# walrus.net
KiCad netlist of a schematic drawn in EAGLE
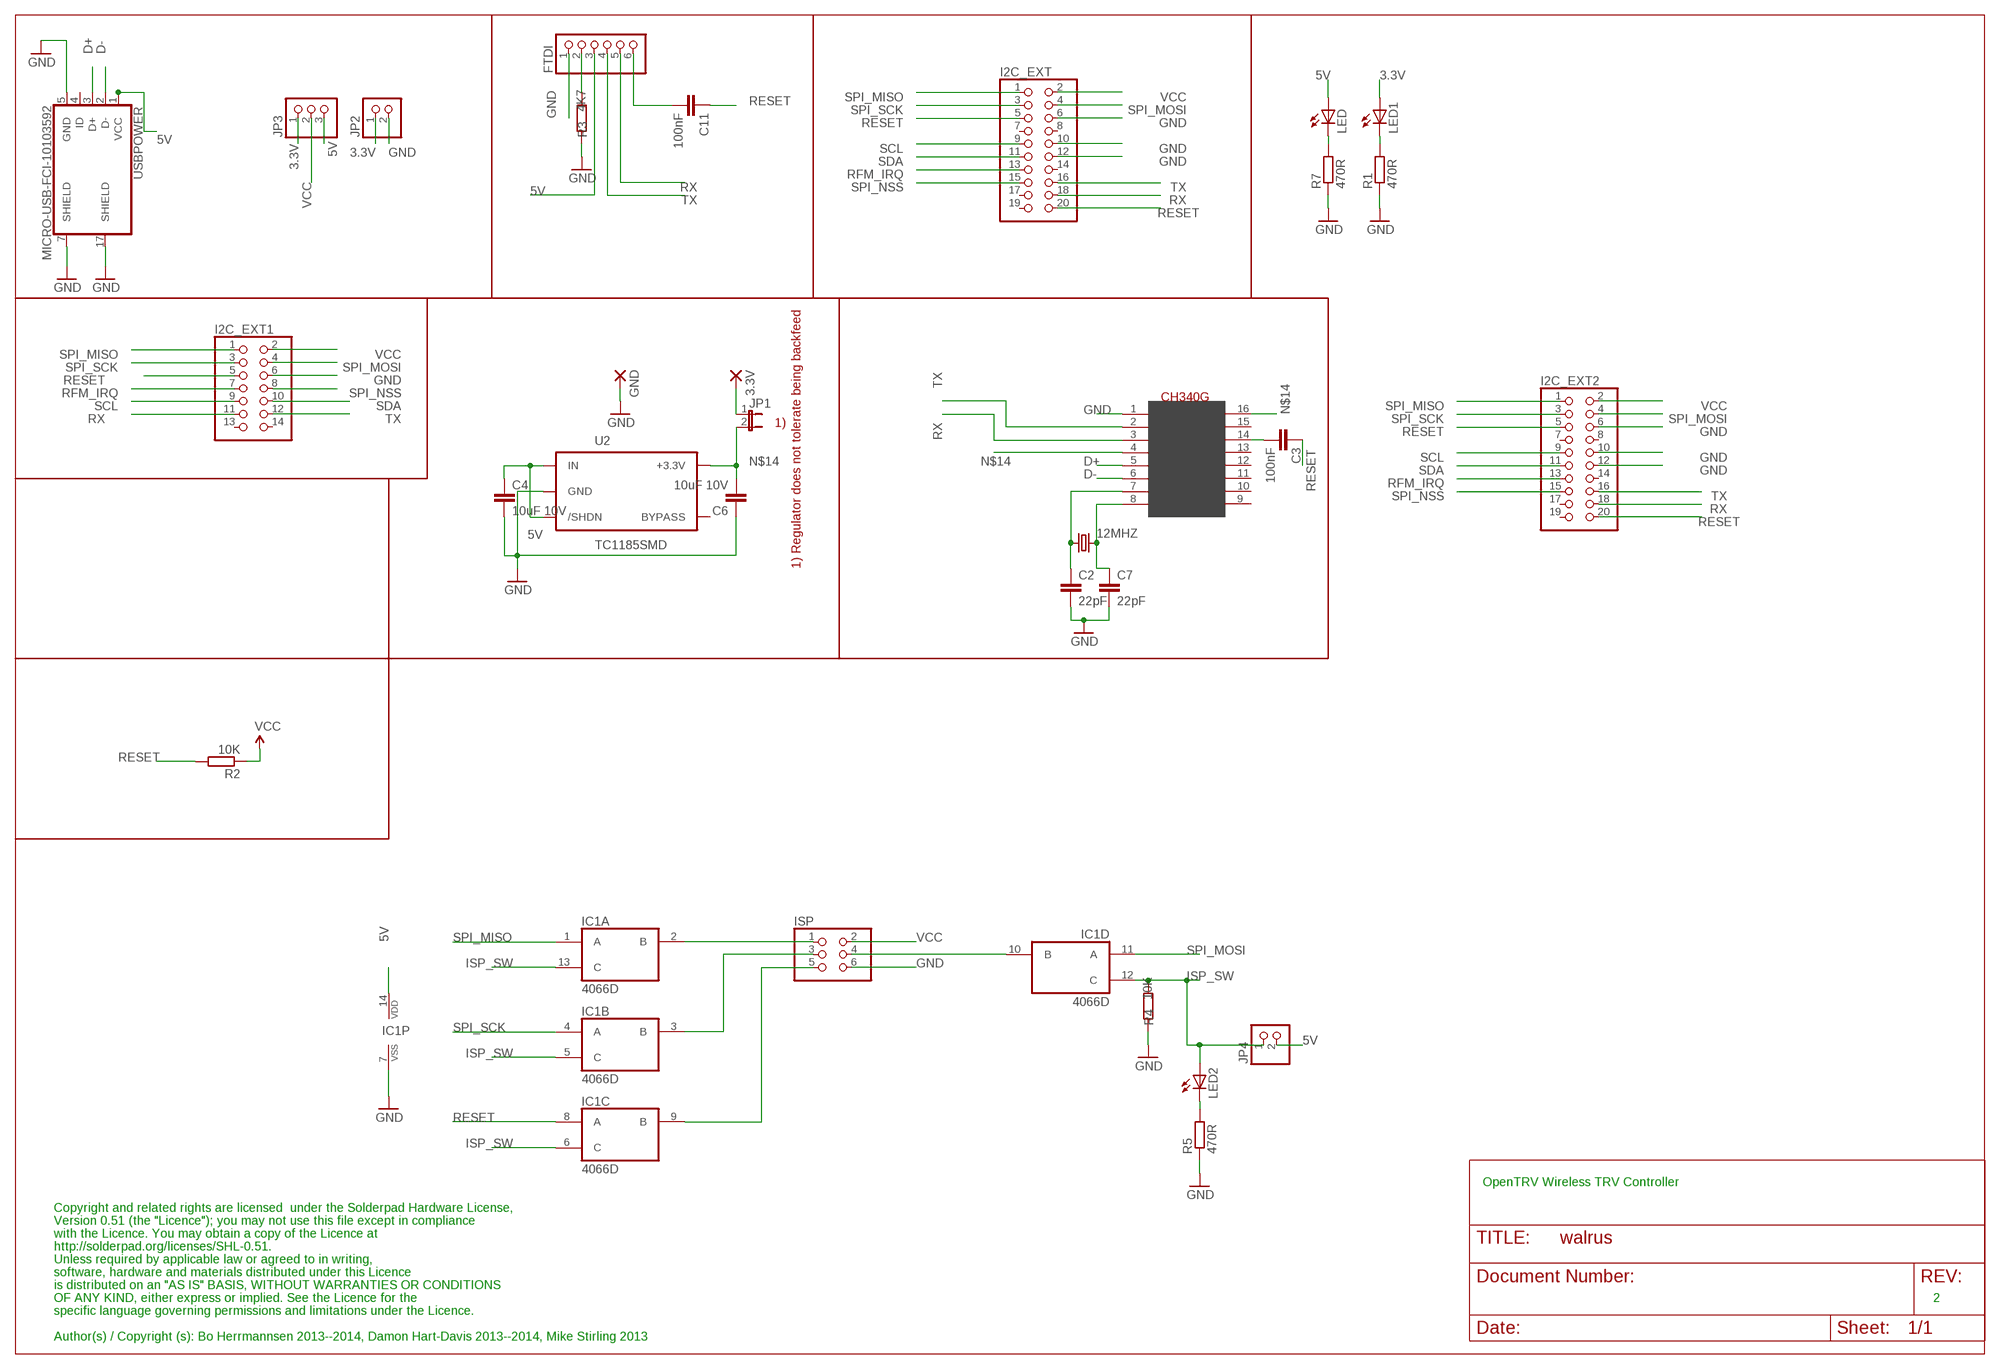
[diagram p0: schematic, sheet 1]

(export (version "E")
  (design (tool "Eeschema 10.0.6"))
  (components
    (comp (ref "3.3V")
      (value "3,81/1,4")
      (footprint "eagle-import:3,81_1,4")
      (libsource (lib "eagle-import") (part "3,81/1,4"))
    )
    (comp (ref "12MHZ")
      (value "CRYSTALHC18U-V")
      (footprint "eagle-import:HC18U-V")
      (libsource (lib "eagle-import") (part "CRYSTALHC18U-V"))
    )
    (comp (ref "C2")
      (value "22pF")
      (footprint "eagle-import:C0603")
      (libsource (lib "eagle-import") (part "C-EUC0603"))
    )
    (comp (ref "C3")
      (value "100nF")
      (footprint "eagle-import:0603-CAP")
      (libsource (lib "eagle-import") (part "CAP0603-CAP"))
    )
    (comp (ref "C4")
      (value "10uF 10V")
      (footprint "eagle-import:0603-CAP")
      (libsource (lib "eagle-import") (part "CAP0603-CAP"))
    )
    (comp (ref "C6")
      (value "10uF 10V")
      (footprint "eagle-import:0603-CAP")
      (libsource (lib "eagle-import") (part "CAP0603-CAP"))
    )
    (comp (ref "C7")
      (value "22pF")
      (footprint "eagle-import:C0603")
      (libsource (lib "eagle-import") (part "C-EUC0603"))
    )
    (comp (ref "C11")
      (value "100nF")
      (footprint "eagle-import:0603-CAP")
      (libsource (lib "eagle-import") (part "CAP0603-CAP"))
    )
    (comp (ref "FTDI")
      (value "PINHD-1X6/90")
      (footprint "eagle-import:1X06_90")
      (libsource (lib "eagle-import") (part "PINHD-1X6/90"))
    )
    (comp (ref "GND")
      (value "3,81/1,4")
      (footprint "eagle-import:3,81_1,4")
      (libsource (lib "eagle-import") (part "3,81/1,4"))
    )
    (comp (ref "I2C_EXT")
      (value "PINHD-2X10")
      (footprint "eagle-import:2X10")
      (libsource (lib "eagle-import") (part "PINHD-2X10"))
    )
    (comp (ref "I2C_EXT1")
      (value "PINHD-2X7")
      (footprint "eagle-import:2X07")
      (libsource (lib "eagle-import") (part "PINHD-2X7"))
    )
    (comp (ref "I2C_EXT2")
      (value "PINHD-2X10")
      (footprint "eagle-import:2X10")
      (libsource (lib "eagle-import") (part "PINHD-2X10"))
    )
    (comp (ref "IC1")
      (value "4066D")
      (footprint "eagle-import:SO14")
      (libsource (lib "eagle-import") (part "4066D"))
    )
    (comp (ref "ISP")
      (value "PINHD-2X3")
      (footprint "eagle-import:2X03")
      (libsource (lib "eagle-import") (part "PINHD-2X3"))
    )
    (comp (ref "JP1")
      (value "JP1E")
      (footprint "eagle-import:JP1")
      (libsource (lib "eagle-import") (part "JP1E"))
    )
    (comp (ref "JP2")
      (value "PINHD-1X2")
      (footprint "eagle-import:1X02")
      (libsource (lib "eagle-import") (part "PINHD-1X2"))
    )
    (comp (ref "JP3")
      (value "PINHD-1X3")
      (footprint "eagle-import:1X03")
      (libsource (lib "eagle-import") (part "PINHD-1X3"))
    )
    (comp (ref "JP4")
      (value "PINHD-1X2")
      (footprint "eagle-import:1X02")
      (libsource (lib "eagle-import") (part "PINHD-1X2"))
    )
    (comp (ref "LED")
      (value "LEDCHIP-LED0603")
      (footprint "eagle-import:CHIP-LED0603")
      (libsource (lib "eagle-import") (part "LEDCHIP-LED0603"))
    )
    (comp (ref "LED1")
      (value "LEDCHIP-LED0603")
      (footprint "eagle-import:CHIP-LED0603")
      (libsource (lib "eagle-import") (part "LEDCHIP-LED0603"))
    )
    (comp (ref "LED2")
      (value "LEDCHIP-LED0603")
      (footprint "eagle-import:CHIP-LED0603")
      (libsource (lib "eagle-import") (part "LEDCHIP-LED0603"))
    )
    (comp (ref "R1")
      (value "470R")
      (footprint "eagle-import:R0603")
      (libsource (lib "eagle-import") (part "R-EU_R0603"))
    )
    (comp (ref "R2")
      (value "10K")
      (footprint "eagle-import:R0603")
      (libsource (lib "eagle-import") (part "R-EU_R0603"))
    )
    (comp (ref "R3")
      (value "4K7")
      (footprint "eagle-import:R0603")
      (libsource (lib "eagle-import") (part "R-EU_R0603"))
    )
    (comp (ref "R4")
      (value "10K")
      (footprint "eagle-import:R0603")
      (libsource (lib "eagle-import") (part "R-EU_R0603"))
    )
    (comp (ref "R5")
      (value "470R")
      (footprint "eagle-import:R0603")
      (libsource (lib "eagle-import") (part "R-EU_R0603"))
    )
    (comp (ref "R7")
      (value "470R")
      (footprint "eagle-import:R0603")
      (libsource (lib "eagle-import") (part "R-EU_R0603"))
    )
    (comp (ref "U$3")
      (value "CH340G")
      (footprint "eagle-import:SOIC16")
      (libsource (lib "eagle-import") (part "CH340G"))
    )
    (comp (ref "U2")
      (value "TC1185SMD")
      (footprint "eagle-import:TC1185")
      (libsource (lib "eagle-import") (part "TC1185SMD"))
    )
    (comp (ref "USBPOWER")
      (value "MICRO-USB-FCI-10103592")
      (footprint "eagle-import:MICRO-USB-FCI-10103592")
      (libsource (lib "eagle-import") (part "MICRO-USB-FCI-10103592"))
    )
  )
  (nets
    (net (code "1") (name "/3.3V") (class "Default")
      (node (ref "3.3V") (pin "1") (pinfunction "P_1") (pintype "passive"))
      (node (ref "JP1") (pin "1") (pinfunction "1_1") (pintype "passive"))
      (node (ref "JP2") (pin "1") (pinfunction "1_1") (pintype "passive"))
      (node (ref "JP3") (pin "1") (pinfunction "1_1") (pintype "passive"))
      (node (ref "LED1") (pin "A") (pinfunction "A_A") (pintype "passive"))
    )
    (net (code "2") (name "/5V") (class "Default")
      (node (ref "C4") (pin "1") (pinfunction "1_1") (pintype "passive"))
      (node (ref "FTDI") (pin "3") (pinfunction "3_3") (pintype "passive"))
      (node (ref "IC1") (pin "14") (pinfunction "VDD_14") (pintype "power_in"))
      (node (ref "JP3") (pin "3") (pinfunction "3_3") (pintype "passive"))
      (node (ref "JP4") (pin "2") (pinfunction "2_2") (pintype "passive"))
      (node (ref "LED") (pin "A") (pinfunction "A_A") (pintype "passive"))
      (node (ref "U2") (pin "1") (pinfunction "IN_1") (pintype "passive"))
      (node (ref "U2") (pin "3") (pinfunction "/SHDN_3") (pintype "passive"))
      (node (ref "USBPOWER") (pin "1") (pinfunction "VCC_1") (pintype "bidirectional"))
    )
    (net (code "3") (name "/D+") (class "Default")
      (node (ref "U$3") (pin "5") (pinfunction "D+_5") (pintype "bidirectional"))
      (node (ref "USBPOWER") (pin "3") (pinfunction "D+_3") (pintype "bidirectional"))
    )
    (net (code "4") (name "/D-") (class "Default")
      (node (ref "U$3") (pin "6") (pinfunction "D-_6") (pintype "bidirectional"))
      (node (ref "USBPOWER") (pin "2") (pinfunction "D-_2") (pintype "bidirectional"))
    )
    (net (code "5") (name "/ISP_SW") (class "Default")
      (node (ref "IC1") (pin "12") (pinfunction "C_12") (pintype "input"))
      (node (ref "IC1") (pin "13") (pinfunction "C_13") (pintype "input"))
      (node (ref "IC1") (pin "5") (pinfunction "C_5") (pintype "input"))
      (node (ref "IC1") (pin "6") (pinfunction "C_6") (pintype "input"))
      (node (ref "JP4") (pin "1") (pinfunction "1_1") (pintype "passive"))
      (node (ref "LED2") (pin "A") (pinfunction "A_A") (pintype "passive"))
      (node (ref "R4") (pin "2") (pinfunction "2_2") (pintype "passive"))
    )
    (net (code "6") (name "/N$14") (class "Default")
      (node (ref "C6") (pin "2") (pinfunction "2_2") (pintype "passive"))
      (node (ref "JP1") (pin "2") (pinfunction "2_2") (pintype "passive"))
      (node (ref "U$3") (pin "16") (pinfunction "VCC_16") (pintype "bidirectional"))
      (node (ref "U$3") (pin "4") (pinfunction "V3_4") (pintype "bidirectional"))
      (node (ref "U2") (pin "5") (pinfunction "+3.3V_5") (pintype "power_in"))
    )
    (net (code "7") (name "/RESET") (class "Default")
      (node (ref "C11") (pin "1") (pinfunction "1_1") (pintype "passive"))
      (node (ref "C3") (pin "1") (pinfunction "1_1") (pintype "passive"))
      (node (ref "I2C_EXT") (pin "20") (pinfunction "20_20") (pintype "passive"))
      (node (ref "I2C_EXT") (pin "5") (pinfunction "5_5") (pintype "passive"))
      (node (ref "I2C_EXT1") (pin "5") (pinfunction "5_5") (pintype "passive"))
      (node (ref "I2C_EXT2") (pin "20") (pinfunction "20_20") (pintype "passive"))
      (node (ref "I2C_EXT2") (pin "5") (pinfunction "5_5") (pintype "passive"))
      (node (ref "IC1") (pin "8") (pinfunction "A_8") (pintype "tri_state"))
      (node (ref "R2") (pin "2") (pinfunction "2_2") (pintype "passive"))
    )
    (net (code "8") (name "/RFM_IRQ") (class "Default")
      (node (ref "I2C_EXT") (pin "13") (pinfunction "13_13") (pintype "passive"))
      (node (ref "I2C_EXT1") (pin "7") (pinfunction "7_7") (pintype "passive"))
      (node (ref "I2C_EXT2") (pin "13") (pinfunction "13_13") (pintype "passive"))
    )
    (net (code "9") (name "/RX") (class "Default")
      (node (ref "FTDI") (pin "5") (pinfunction "5_5") (pintype "passive"))
      (node (ref "I2C_EXT") (pin "18") (pinfunction "18_18") (pintype "passive"))
      (node (ref "I2C_EXT1") (pin "11") (pinfunction "11_11") (pintype "passive"))
      (node (ref "I2C_EXT2") (pin "18") (pinfunction "18_18") (pintype "passive"))
      (node (ref "U$3") (pin "3") (pinfunction "RX_3") (pintype "bidirectional"))
    )
    (net (code "10") (name "/SCL") (class "Default")
      (node (ref "I2C_EXT") (pin "9") (pinfunction "9_9") (pintype "passive"))
      (node (ref "I2C_EXT1") (pin "9") (pinfunction "9_9") (pintype "passive"))
      (node (ref "I2C_EXT2") (pin "9") (pinfunction "9_9") (pintype "passive"))
    )
    (net (code "11") (name "/SDA") (class "Default")
      (node (ref "I2C_EXT") (pin "11") (pinfunction "11_11") (pintype "passive"))
      (node (ref "I2C_EXT1") (pin "10") (pinfunction "10_10") (pintype "passive"))
      (node (ref "I2C_EXT2") (pin "11") (pinfunction "11_11") (pintype "passive"))
    )
    (net (code "12") (name "/SPI_MISO") (class "Default")
      (node (ref "I2C_EXT") (pin "1") (pinfunction "1_1") (pintype "passive"))
      (node (ref "I2C_EXT1") (pin "1") (pinfunction "1_1") (pintype "passive"))
      (node (ref "I2C_EXT2") (pin "1") (pinfunction "1_1") (pintype "passive"))
      (node (ref "IC1") (pin "1") (pinfunction "A_1") (pintype "tri_state"))
    )
    (net (code "13") (name "/SPI_MOSI") (class "Default")
      (node (ref "I2C_EXT") (pin "4") (pinfunction "4_4") (pintype "passive"))
      (node (ref "I2C_EXT1") (pin "4") (pinfunction "4_4") (pintype "passive"))
      (node (ref "I2C_EXT2") (pin "4") (pinfunction "4_4") (pintype "passive"))
      (node (ref "IC1") (pin "11") (pinfunction "A_11") (pintype "tri_state"))
    )
    (net (code "14") (name "/SPI_NSS") (class "Default")
      (node (ref "I2C_EXT") (pin "15") (pinfunction "15_15") (pintype "passive"))
      (node (ref "I2C_EXT1") (pin "8") (pinfunction "8_8") (pintype "passive"))
      (node (ref "I2C_EXT2") (pin "15") (pinfunction "15_15") (pintype "passive"))
    )
    (net (code "15") (name "/SPI_SCK") (class "Default")
      (node (ref "I2C_EXT") (pin "3") (pinfunction "3_3") (pintype "passive"))
      (node (ref "I2C_EXT1") (pin "3") (pinfunction "3_3") (pintype "passive"))
      (node (ref "I2C_EXT2") (pin "3") (pinfunction "3_3") (pintype "passive"))
      (node (ref "IC1") (pin "4") (pinfunction "A_4") (pintype "tri_state"))
    )
    (net (code "16") (name "/TX") (class "Default")
      (node (ref "FTDI") (pin "4") (pinfunction "4_4") (pintype "passive"))
      (node (ref "I2C_EXT") (pin "16") (pinfunction "16_16") (pintype "passive"))
      (node (ref "I2C_EXT1") (pin "12") (pinfunction "12_12") (pintype "passive"))
      (node (ref "I2C_EXT2") (pin "16") (pinfunction "16_16") (pintype "passive"))
      (node (ref "U$3") (pin "2") (pinfunction "TX_2") (pintype "bidirectional"))
    )
    (net (code "17") (name "GND") (class "Default")
      (node (ref "C2") (pin "2") (pinfunction "2_2") (pintype "passive"))
      (node (ref "C4") (pin "2") (pinfunction "2_2") (pintype "passive"))
      (node (ref "C6") (pin "1") (pinfunction "1_1") (pintype "passive"))
      (node (ref "C7") (pin "2") (pinfunction "2_2") (pintype "passive"))
      (node (ref "FTDI") (pin "1") (pinfunction "1_1") (pintype "passive"))
      (node (ref "GND") (pin "1") (pinfunction "P_1") (pintype "passive"))
      (node (ref "I2C_EXT") (pin "10") (pinfunction "10_10") (pintype "passive"))
      (node (ref "I2C_EXT") (pin "12") (pinfunction "12_12") (pintype "passive"))
      (node (ref "I2C_EXT") (pin "6") (pinfunction "6_6") (pintype "passive"))
      (node (ref "I2C_EXT1") (pin "6") (pinfunction "6_6") (pintype "passive"))
      (node (ref "I2C_EXT2") (pin "10") (pinfunction "10_10") (pintype "passive"))
      (node (ref "I2C_EXT2") (pin "12") (pinfunction "12_12") (pintype "passive"))
      (node (ref "I2C_EXT2") (pin "6") (pinfunction "6_6") (pintype "passive"))
      (node (ref "IC1") (pin "7") (pinfunction "VSS_7") (pintype "power_in"))
      (node (ref "ISP") (pin "6") (pinfunction "6_6") (pintype "passive"))
      (node (ref "JP2") (pin "2") (pinfunction "2_2") (pintype "passive"))
      (node (ref "R1") (pin "1") (pinfunction "1_1") (pintype "passive"))
      (node (ref "R3") (pin "1") (pinfunction "1_1") (pintype "passive"))
      (node (ref "R4") (pin "1") (pinfunction "1_1") (pintype "passive"))
      (node (ref "R5") (pin "1") (pinfunction "1_1") (pintype "passive"))
      (node (ref "R7") (pin "1") (pinfunction "1_1") (pintype "passive"))
      (node (ref "U$3") (pin "1") (pinfunction "GND_1") (pintype "bidirectional"))
      (node (ref "U2") (pin "2") (pinfunction "GND_2") (pintype "passive"))
      (node (ref "USBPOWER") (pin "17") (pinfunction "SHIELD_17") (pintype "bidirectional"))
      (node (ref "USBPOWER") (pin "5") (pinfunction "GND_5") (pintype "bidirectional"))
      (node (ref "USBPOWER") (pin "7") (pinfunction "SHIELD_7") (pintype "bidirectional"))
    )
    (net (code "18") (name "Net-(C11-Pad2)") (class "Default")
      (node (ref "C11") (pin "2") (pinfunction "2_2") (pintype "passive"))
      (node (ref "FTDI") (pin "6") (pinfunction "6_6") (pintype "passive"))
    )
    (net (code "19") (name "Net-(FTDI-Pad2)") (class "Default")
      (node (ref "FTDI") (pin "2") (pinfunction "2_2") (pintype "passive"))
      (node (ref "R3") (pin "2") (pinfunction "2_2") (pintype "passive"))
    )
    (net (code "20") (name "Net-(IC1A-B)") (class "Default")
      (node (ref "IC1") (pin "2") (pinfunction "B_2") (pintype "tri_state"))
      (node (ref "ISP") (pin "1") (pinfunction "1_1") (pintype "passive"))
    )
    (net (code "21") (name "Net-(IC1B-B)") (class "Default")
      (node (ref "IC1") (pin "3") (pinfunction "B_3") (pintype "tri_state"))
      (node (ref "ISP") (pin "3") (pinfunction "3_3") (pintype "passive"))
    )
    (net (code "22") (name "Net-(IC1C-B)") (class "Default")
      (node (ref "IC1") (pin "9") (pinfunction "B_9") (pintype "tri_state"))
      (node (ref "ISP") (pin "5") (pinfunction "5_5") (pintype "passive"))
    )
    (net (code "23") (name "Net-(IC1D-B)") (class "Default")
      (node (ref "IC1") (pin "10") (pinfunction "B_10") (pintype "tri_state"))
      (node (ref "ISP") (pin "4") (pinfunction "4_4") (pintype "passive"))
    )
    (net (code "24") (name "Net-(LED-PadC)") (class "Default")
      (node (ref "LED") (pin "C") (pinfunction "C_C") (pintype "passive"))
      (node (ref "R7") (pin "2") (pinfunction "2_2") (pintype "passive"))
    )
    (net (code "25") (name "Net-(LED1-PadC)") (class "Default")
      (node (ref "LED1") (pin "C") (pinfunction "C_C") (pintype "passive"))
      (node (ref "R1") (pin "2") (pinfunction "2_2") (pintype "passive"))
    )
    (net (code "26") (name "Net-(LED2-PadC)") (class "Default")
      (node (ref "LED2") (pin "C") (pinfunction "C_C") (pintype "passive"))
      (node (ref "R5") (pin "2") (pinfunction "2_2") (pintype "passive"))
    )
    (net (code "27") (name "Net-(U$3-RTS)") (class "Default")
      (node (ref "C3") (pin "2") (pinfunction "2_2") (pintype "passive"))
      (node (ref "U$3") (pin "14") (pinfunction "RTS_14") (pintype "bidirectional"))
    )
    (net (code "28") (name "Net-(U$3-XI)") (class "Default")
      (node (ref "12MHZ") (pin "1") (pinfunction "1_1") (pintype "passive"))
      (node (ref "C2") (pin "1") (pinfunction "1_1") (pintype "passive"))
      (node (ref "U$3") (pin "7") (pinfunction "XI_7") (pintype "bidirectional"))
    )
    (net (code "29") (name "Net-(U$3-XO)") (class "Default")
      (node (ref "12MHZ") (pin "2") (pinfunction "2_2") (pintype "passive"))
      (node (ref "C7") (pin "1") (pinfunction "1_1") (pintype "passive"))
      (node (ref "U$3") (pin "8") (pinfunction "XO_8") (pintype "bidirectional"))
    )
    (net (code "30") (name "VCC") (class "Default")
      (node (ref "I2C_EXT") (pin "2") (pinfunction "2_2") (pintype "passive"))
      (node (ref "I2C_EXT1") (pin "2") (pinfunction "2_2") (pintype "passive"))
      (node (ref "I2C_EXT2") (pin "2") (pinfunction "2_2") (pintype "passive"))
      (node (ref "ISP") (pin "2") (pinfunction "2_2") (pintype "passive"))
      (node (ref "JP3") (pin "2") (pinfunction "2_2") (pintype "passive"))
      (node (ref "R2") (pin "1") (pinfunction "1_1") (pintype "passive"))
    )
    (net (code "31") (name "unconnected-(I2C_EXT-Pad7)") (class "Default")
      (node (ref "I2C_EXT") (pin "7") (pinfunction "7_7") (pintype "passive"))
    )
    (net (code "32") (name "unconnected-(I2C_EXT-Pad8)") (class "Default")
      (node (ref "I2C_EXT") (pin "8") (pinfunction "8_8") (pintype "passive"))
    )
    (net (code "33") (name "unconnected-(I2C_EXT-Pad14)") (class "Default")
      (node (ref "I2C_EXT") (pin "14") (pinfunction "14_14") (pintype "passive"))
    )
    (net (code "34") (name "unconnected-(I2C_EXT-Pad17)") (class "Default")
      (node (ref "I2C_EXT") (pin "17") (pinfunction "17_17") (pintype "passive"))
    )
    (net (code "35") (name "unconnected-(I2C_EXT-Pad19)") (class "Default")
      (node (ref "I2C_EXT") (pin "19") (pinfunction "19_19") (pintype "passive"))
    )
    (net (code "36") (name "unconnected-(I2C_EXT1-Pad13)") (class "Default")
      (node (ref "I2C_EXT1") (pin "13") (pinfunction "13_13") (pintype "passive"))
    )
    (net (code "37") (name "unconnected-(I2C_EXT1-Pad14)") (class "Default")
      (node (ref "I2C_EXT1") (pin "14") (pinfunction "14_14") (pintype "passive"))
    )
    (net (code "38") (name "unconnected-(I2C_EXT2-Pad7)") (class "Default")
      (node (ref "I2C_EXT2") (pin "7") (pinfunction "7_7") (pintype "passive"))
    )
    (net (code "39") (name "unconnected-(I2C_EXT2-Pad8)") (class "Default")
      (node (ref "I2C_EXT2") (pin "8") (pinfunction "8_8") (pintype "passive"))
    )
    (net (code "40") (name "unconnected-(I2C_EXT2-Pad14)") (class "Default")
      (node (ref "I2C_EXT2") (pin "14") (pinfunction "14_14") (pintype "passive"))
    )
    (net (code "41") (name "unconnected-(I2C_EXT2-Pad17)") (class "Default")
      (node (ref "I2C_EXT2") (pin "17") (pinfunction "17_17") (pintype "passive"))
    )
    (net (code "42") (name "unconnected-(I2C_EXT2-Pad19)") (class "Default")
      (node (ref "I2C_EXT2") (pin "19") (pinfunction "19_19") (pintype "passive"))
    )
    (net (code "43") (name "unconnected-(U$3-CTS-Pad9)") (class "Default")
      (node (ref "U$3") (pin "9") (pinfunction "CTS_9") (pintype "bidirectional"))
    )
    (net (code "44") (name "unconnected-(U$3-DCD-Pad12)") (class "Default")
      (node (ref "U$3") (pin "12") (pinfunction "DCD_12") (pintype "bidirectional"))
    )
    (net (code "45") (name "unconnected-(U$3-DSR-Pad10)") (class "Default")
      (node (ref "U$3") (pin "10") (pinfunction "DSR_10") (pintype "bidirectional"))
    )
    (net (code "46") (name "unconnected-(U$3-DTR-Pad13)") (class "Default")
      (node (ref "U$3") (pin "13") (pinfunction "DTR_13") (pintype "bidirectional"))
    )
    (net (code "47") (name "unconnected-(U$3-RI-Pad11)") (class "Default")
      (node (ref "U$3") (pin "11") (pinfunction "RI_11") (pintype "bidirectional"))
    )
    (net (code "48") (name "unconnected-(U$3-RS232-Pad15)") (class "Default")
      (node (ref "U$3") (pin "15") (pinfunction "RS232_15") (pintype "bidirectional"))
    )
    (net (code "49") (name "unconnected-(U2-BYPASS-Pad4)") (class "Default")
      (node (ref "U2") (pin "4") (pinfunction "BYPASS_4") (pintype "passive"))
    )
    (net (code "50") (name "unconnected-(USBPOWER-ID-Pad4)") (class "Default")
      (node (ref "USBPOWER") (pin "4") (pinfunction "ID_4") (pintype "bidirectional"))
    )
  )
)
